# RackEth_rev_1.net
KiCad netlist of a schematic drawn in EasyEDA Pro
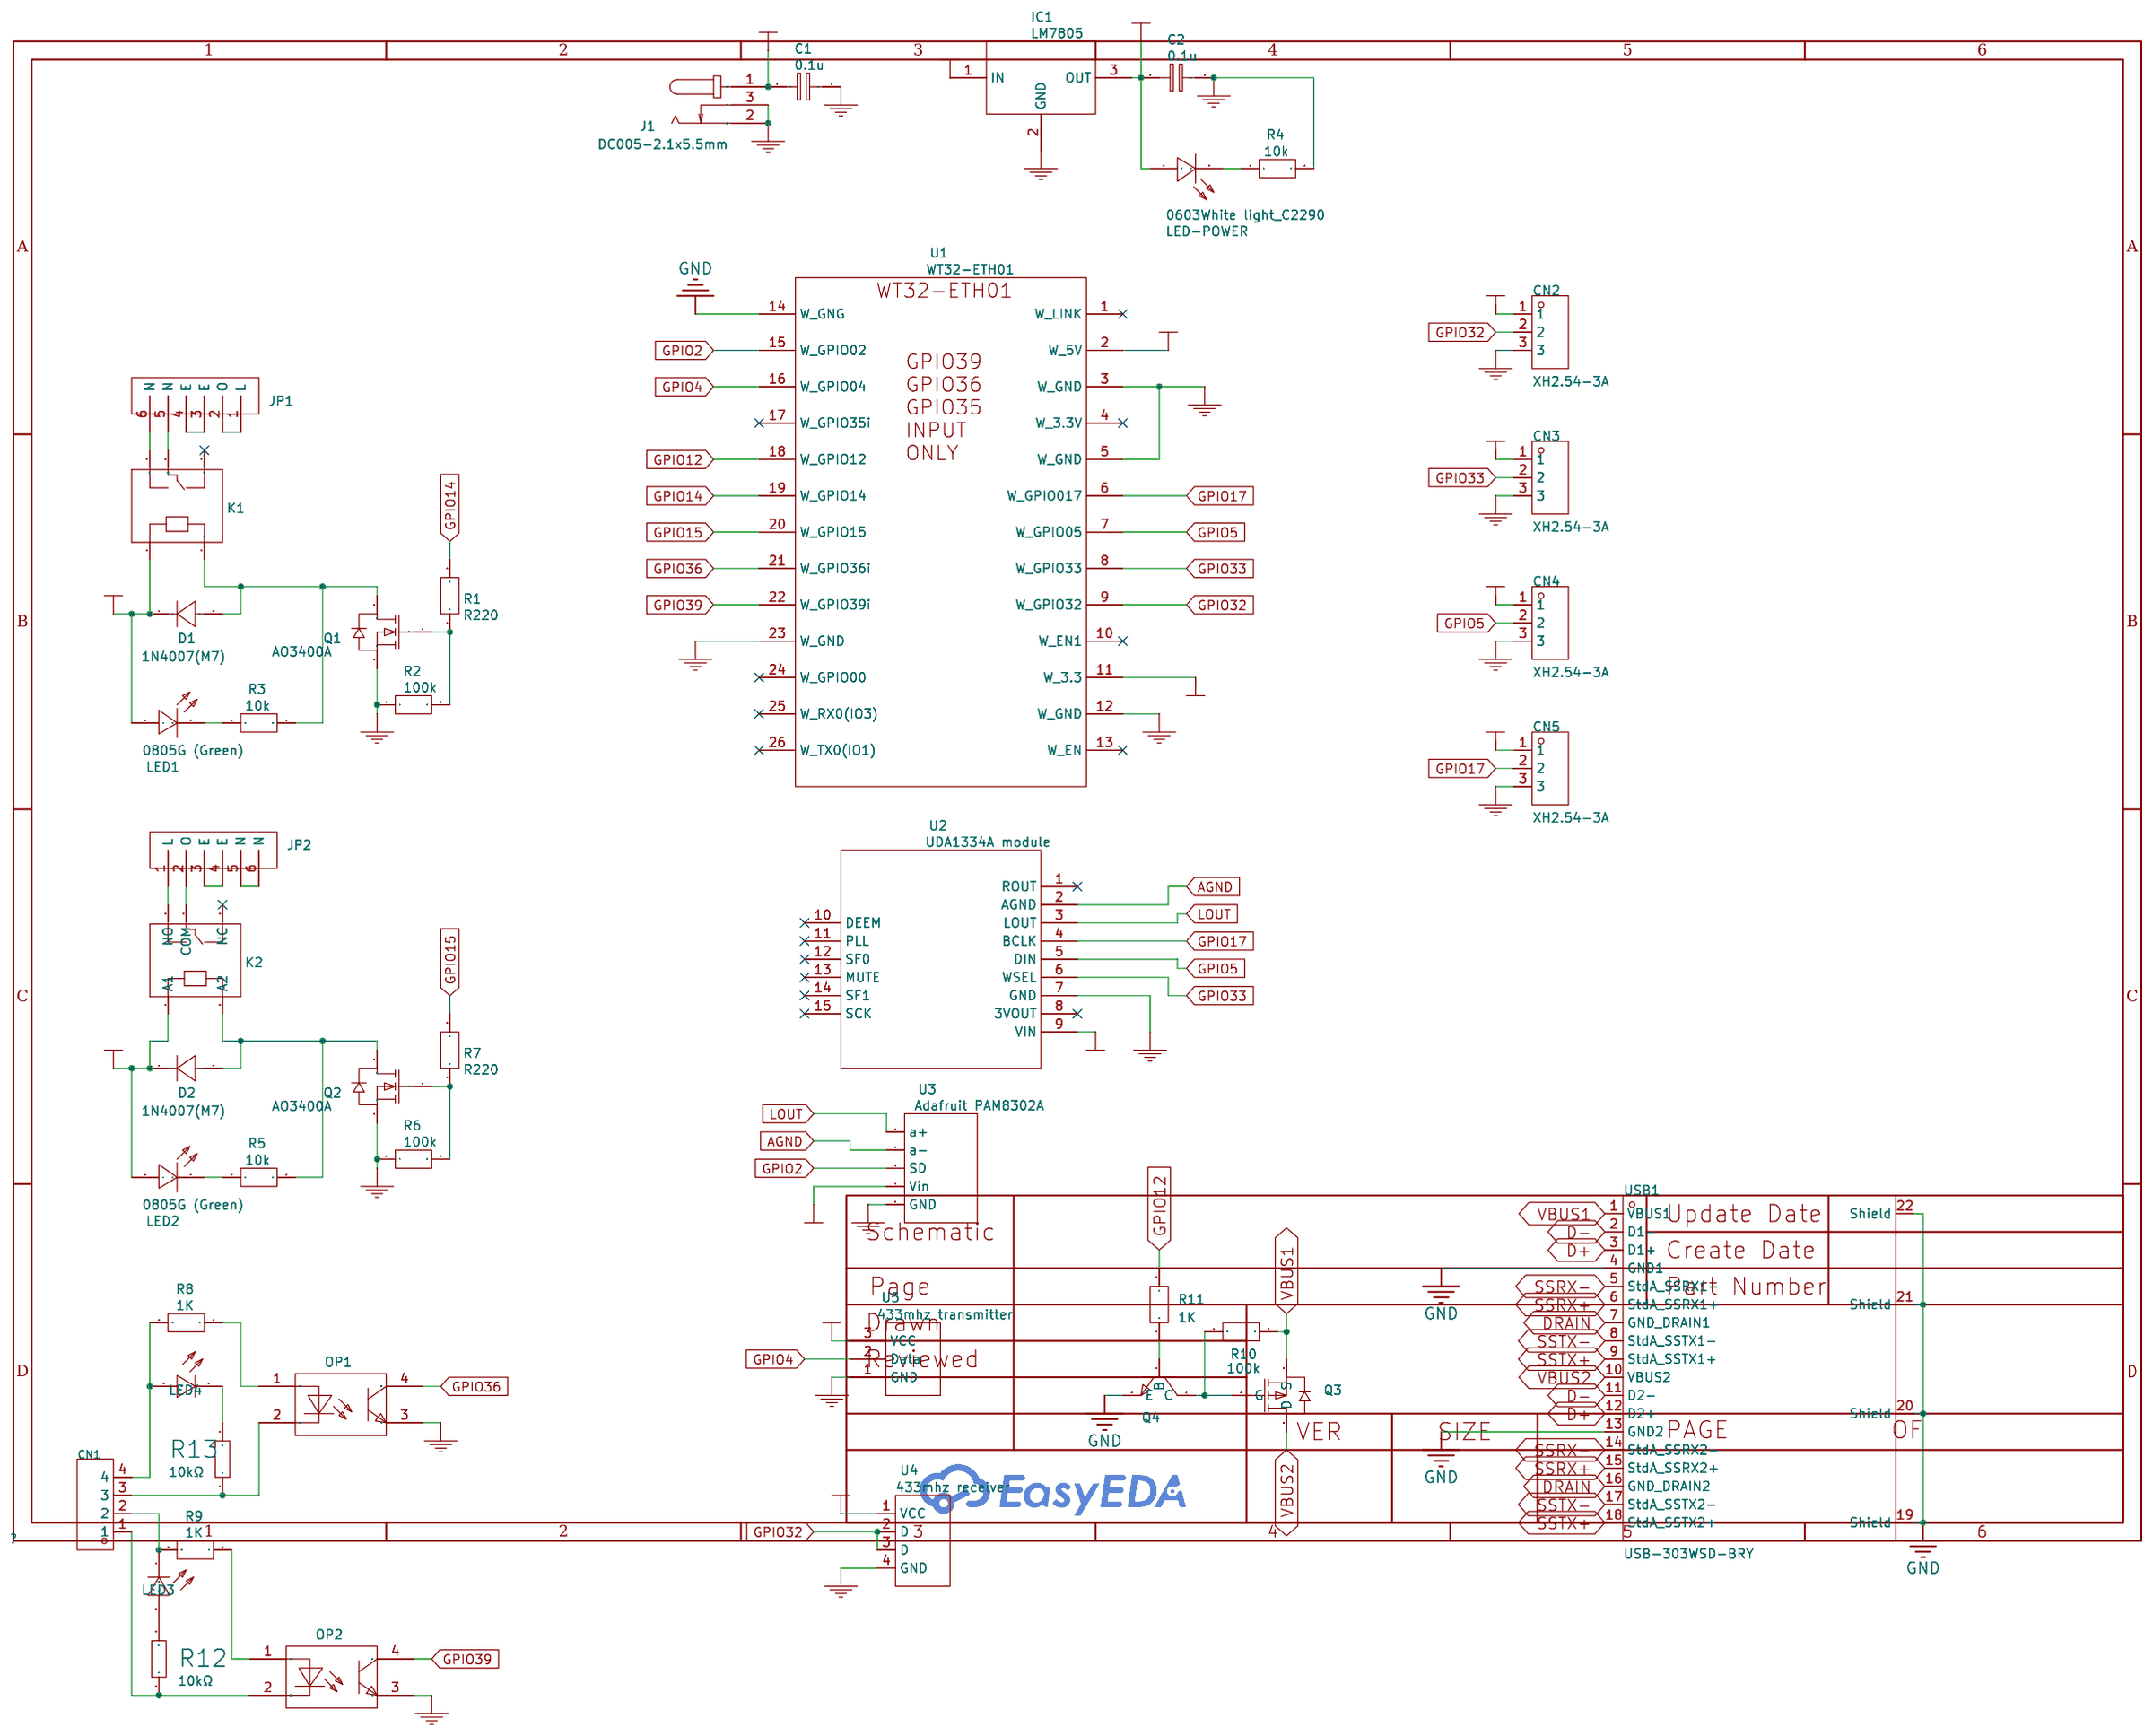
[diagram p0: schematic sheet]

(export (version "E")
  (design (tool "Eeschema 10.0.6"))
  (components
    (comp (ref "C1")
      (value "0.1u")
      (footprint "easyedapro:C0603")
      (fields
        (field (name "Manufacturer Part") "CL05B104KO5NNNC")
        (field (name "Manufacturer") "SAMSUNG(三星)")
      )
      (libsource (lib "easyedapro") (part "0.1u"))
    )
    (comp (ref "C2")
      (value "0.1u")
      (footprint "easyedapro:C0603")
      (fields
        (field (name "Manufacturer Part") "CL05B104KO5NNNC")
        (field (name "Manufacturer") "SAMSUNG(三星)")
      )
      (libsource (lib "easyedapro") (part "0.1u"))
    )
    (comp (ref "CN1")
      (value "WJ127-5.0-4P")
      (footprint "easyedapro:CONN-TH_4P-P5.00_WJ127-5.0-4P")
      (fields (field (name "Manufacturer") "KANGNEX(康奈克斯电气)"))
      (libsource (lib "easyedapro") (part "WJ127-5.0-4P"))
    )
    (comp (ref "CN2")
      (value "XH2.54-3A")
      (footprint "easyedapro:CONN-TH_3P-P2.50_HCTL_XH-3A-L")
      (libsource (lib "easyedapro") (part "XH2.54-3A"))
    )
    (comp (ref "CN3")
      (value "XH2.54-3A")
      (footprint "easyedapro:CONN-TH_3P-P2.50_HCTL_XH-3A-L")
      (libsource (lib "easyedapro") (part "XH2.54-3A"))
    )
    (comp (ref "CN4")
      (value "XH2.54-3A")
      (footprint "easyedapro:CONN-TH_3P-P2.50_HCTL_XH-3A-L")
      (libsource (lib "easyedapro") (part "XH2.54-3A"))
    )
    (comp (ref "CN5")
      (value "XH2.54-3A")
      (footprint "easyedapro:CONN-TH_3P-P2.50_HCTL_XH-3A-L")
      (libsource (lib "easyedapro") (part "XH2.54-3A"))
    )
    (comp (ref "D1")
      (value "1N4007(M7)")
      (footprint "easyedapro:SMA_L4.3-W2.7-LS5.1-RD")
      (fields (field (name "Manufacturer") "UMW(友台半导体)"))
      (libsource (lib "easyedapro") (part "1N4007(M7)"))
    )
    (comp (ref "D2")
      (value "1N4007(M7)")
      (footprint "easyedapro:SMA_L4.3-W2.7-LS5.1-RD")
      (fields (field (name "Manufacturer") "UMW(友台半导体)"))
      (libsource (lib "easyedapro") (part "1N4007(M7)"))
    )
    (comp (ref "IC1")
      (value "LM7805")
      (footprint "easyedapro:LM7805")
      (libsource (lib "easyedapro") (part "LM7805"))
    )
    (comp (ref "J1")
      (value "DC005-2.1x5.5mm")
      (footprint "easyedapro:DC-IN-TH_POWER-JACK")
      (fields (field (name "Manufacturer Part") "POWER-JACK") (field (name "Manufacturer") "索峰"))
      (libsource (lib "easyedapro") (part "DC005-2.1x5.5mm"))
    )
    (comp (ref "JP1") (value "JP1") (libsource (lib "easyedapro") (part "Terminal?")))
    (comp (ref "JP2") (value "JP2") (libsource (lib "easyedapro") (part "Terminal?")))
    (comp (ref "K1")
      (value "Relay1")
      (footprint "easyedapro:SRD-05VDC-SL-C_RELAY_SRD-05VDC-SL-C")
      (libsource (lib "easyedapro") (part "Relay1"))
    )
    (comp (ref "K2")
      (value "Relay2")
      (footprint "easyedapro:SRD-05VDC-SL-C_RELAY_SRD-05VDC-SL-C")
      (libsource (lib "easyedapro") (part "Relay2"))
    )
    (comp (ref "LED-POWER")
      (value "0603White light_C2290")
      (footprint "easyedapro:LED0603-R-RD_WHITE")
      (fields (field (name "Manufacturer Part") "KT-0603W") (field (name "Manufacturer") "KENTO"))
      (libsource (lib "easyedapro") (part "0603White light_C2290"))
    )
    (comp (ref "LED1")
      (value "0805G (Green)")
      (footprint "easyedapro:LED0805-RD_GREEN")
      (fields (field (name "Manufacturer") "KENTO"))
      (libsource (lib "easyedapro") (part "0805G (Green)"))
    )
    (comp (ref "LED2")
      (value "0805G (Green)")
      (footprint "easyedapro:LED0805-RD_GREEN")
      (fields (field (name "Manufacturer") "KENTO"))
      (libsource (lib "easyedapro") (part "0805G (Green)"))
    )
    (comp (ref "LED3")
      (value "19-213/Y2C-CQ2R2L/3T(CY)")
      (footprint "easyedapro:LED0603-RD-YELLOW")
      (fields (field (name "Manufacturer") "EVERLIGHT(亿光)"))
      (libsource (lib "easyedapro") (part "19-213/Y2C-CQ2R2L/3T(CY)"))
    )
    (comp (ref "LED4")
      (value "19-213/Y2C-CQ2R2L/3T(CY)")
      (footprint "easyedapro:LED0603-RD-YELLOW")
      (fields (field (name "Manufacturer") "EVERLIGHT(亿光)"))
      (libsource (lib "easyedapro") (part "19-213/Y2C-CQ2R2L/3T(CY)"))
    )
    (comp (ref "OP1")
      (value "EL817S1(C)(TU)-F")
      (footprint "easyedapro:OPTO-SMD-4_L4.6-W6.5-P2.54-LS10.3-TL")
      (fields (field (name "Manufacturer") "EVERLIGHT(亿光)"))
      (libsource (lib "easyedapro") (part "EL817S1(C)(TU)-F"))
    )
    (comp (ref "OP2")
      (value "EL817S1(C)(TU)-F")
      (footprint "easyedapro:OPTO-SMD-4_L4.6-W6.5-P2.54-LS10.3-TL")
      (fields (field (name "Manufacturer") "EVERLIGHT(亿光)"))
      (libsource (lib "easyedapro") (part "EL817S1(C)(TU)-F"))
    )
    (comp (ref "Q1")
      (value "AO3400A")
      (footprint "easyedapro:SOT-23-3_L2.9-W1.6-P1.90-LS2.8-BR")
      (fields (field (name "Manufacturer") "AOS"))
      (libsource (lib "easyedapro") (part "AO3400A"))
    )
    (comp (ref "Q2")
      (value "AO3400A")
      (footprint "easyedapro:SOT-23-3_L2.9-W1.6-P1.90-LS2.8-BR")
      (fields (field (name "Manufacturer") "AOS"))
      (libsource (lib "easyedapro") (part "AO3400A"))
    )
    (comp (ref "Q3")
      (value "AO3401A")
      (footprint "easyedapro:SOT-23_L2.9-W1.3-P1.90-LS2.4-BR")
      (fields (field (name "Manufacturer") "AOS"))
      (libsource (lib "easyedapro") (part "AO3401A"))
    )
    (comp (ref "Q4")
      (value "MMBT3904(RANGE:100-300)")
      (footprint "easyedapro:SOT-23-3_L2.9-W1.3-P1.90-LS2.4-BR")
      (fields (field (name "Manufacturer") "CJ(江苏长电/长晶)"))
      (libsource (lib "easyedapro") (part "MMBT3904"))
    )
    (comp (ref "R1")
      (value "R220")
      (footprint "easyedapro:R0603")
      (fields
        (field (name "Manufacturer Part") "0603WAF2200T5E")
        (field (name "Manufacturer") "UNI-ROYAL(厚声)")
      )
      (libsource (lib "easyedapro") (part "R220"))
    )
    (comp (ref "R2")
      (value "100k")
      (footprint "easyedapro:R0603")
      (fields
        (field (name "Manufacturer Part") "0603WAF1003T5E")
        (field (name "Manufacturer") "UNI-ROYAL(厚声)")
      )
      (libsource (lib "easyedapro") (part "100k"))
    )
    (comp (ref "R3")
      (value "10k")
      (footprint "easyedapro:R0603")
      (fields
        (field (name "Manufacturer Part") "0603WAF1002T5E")
        (field (name "Manufacturer") "UNI-ROYAL(厚声)")
      )
      (libsource (lib "easyedapro") (part "10k"))
    )
    (comp (ref "R4")
      (value "10k")
      (footprint "easyedapro:R0603")
      (fields
        (field (name "Manufacturer Part") "0603WAF1002T5E")
        (field (name "Manufacturer") "UNI-ROYAL(厚声)")
      )
      (libsource (lib "easyedapro") (part "10k"))
    )
    (comp (ref "R5")
      (value "10k")
      (footprint "easyedapro:R0603")
      (fields
        (field (name "Manufacturer Part") "0603WAF1002T5E")
        (field (name "Manufacturer") "UNI-ROYAL(厚声)")
      )
      (libsource (lib "easyedapro") (part "10k"))
    )
    (comp (ref "R6")
      (value "100k")
      (footprint "easyedapro:R0603")
      (fields
        (field (name "Manufacturer Part") "0603WAF1003T5E")
        (field (name "Manufacturer") "UNI-ROYAL(厚声)")
      )
      (libsource (lib "easyedapro") (part "100k"))
    )
    (comp (ref "R7")
      (value "R220")
      (footprint "easyedapro:R0603")
      (fields
        (field (name "Manufacturer Part") "0603WAF2200T5E")
        (field (name "Manufacturer") "UNI-ROYAL(厚声)")
      )
      (libsource (lib "easyedapro") (part "R220"))
    )
    (comp (ref "R8")
      (value "1K")
      (footprint "easyedapro:R0603")
      (fields
        (field (name "Manufacturer Part") "0603WAF2200T5E")
        (field (name "Manufacturer") "UNI-ROYAL(厚声)")
      )
      (libsource (lib "easyedapro") (part "1K"))
    )
    (comp (ref "R9")
      (value "1K")
      (footprint "easyedapro:R0603")
      (fields
        (field (name "Manufacturer Part") "0603WAF2200T5E")
        (field (name "Manufacturer") "UNI-ROYAL(厚声)")
      )
      (libsource (lib "easyedapro") (part "1K"))
    )
    (comp (ref "R10")
      (value "100k")
      (footprint "easyedapro:R0603")
      (fields
        (field (name "Manufacturer Part") "0603WAF1003T5E")
        (field (name "Manufacturer") "UNI-ROYAL(厚声)")
      )
      (libsource (lib "easyedapro") (part "100k"))
    )
    (comp (ref "R11")
      (value "1K")
      (footprint "easyedapro:R0603")
      (fields
        (field (name "Manufacturer Part") "0603WAF2200T5E")
        (field (name "Manufacturer") "UNI-ROYAL(厚声)")
      )
      (libsource (lib "easyedapro") (part "1K"))
    )
    (comp (ref "R12")
      (value "10kΩ")
      (footprint "easyedapro:R0603")
      (fields
        (field (name "Manufacturer Part") "0603WAF1002T5E")
        (field (name "Manufacturer") "UNI-ROYAL(厚声)")
      )
      (libsource (lib "easyedapro") (part "0603WAF1002T5E"))
    )
    (comp (ref "R13")
      (value "10kΩ")
      (footprint "easyedapro:R0603")
      (fields
        (field (name "Manufacturer Part") "0603WAF1002T5E")
        (field (name "Manufacturer") "UNI-ROYAL(厚声)")
      )
      (libsource (lib "easyedapro") (part "0603WAF1002T5E"))
    )
    (comp (ref "U1")
      (value "WT32-ETH01")
      (footprint "easyedapro:WT32-ETH01-M")
      (fields (field (name "Manufacturer") "Wireless-Tag"))
      (libsource (lib "easyedapro") (part "WT32-ETH01"))
    )
    (comp (ref "U2")
      (value "UDA1334A module")
      (footprint "easyedapro:UDA1334A_MODULE")
      (libsource (lib "easyedapro") (part "UDA1334A module"))
    )
    (comp (ref "U3")
      (value "Adafruit PAM8302A")
      (footprint "easyedapro:ADAFRUIT PAM8302A")
      (libsource (lib "easyedapro") (part "Adafruit PAM8302A"))
    )
    (comp (ref "U4")
      (value "433mhz receiver")
      (footprint "easyedapro:433MHZ-RECEIVER-PINS")
      (libsource (lib "easyedapro") (part "433mhz receiver"))
    )
    (comp (ref "U5")
      (value "433mhz transmitter")
      (footprint "easyedapro:RF-TRANSMITTER (433MHZ)")
      (libsource (lib "easyedapro") (part "433mhz transmitter"))
    )
    (comp (ref "USB1")
      (value "USB-303WSD-BRY")
      (footprint "easyedapro:USB-A-TH_XUNPU_USB-303WSD-BRY")
      (fields (field (name "Manufacturer") "XUNPU(讯普)"))
      (libsource (lib "easyedapro") (part "USB-303WSD-BRY"))
    )
  )
  (nets
    (net (code "1") (name "+3.3V") (class "Default")
      (node (ref "CN2") (pin "1") (pinfunction "1_1") (pintype "unspecified"))
      (node (ref "CN3") (pin "1") (pinfunction "1_1") (pintype "unspecified"))
      (node (ref "CN4") (pin "1") (pinfunction "1_1") (pintype "unspecified"))
      (node (ref "CN5") (pin "1") (pinfunction "1_1") (pintype "unspecified"))
      (node (ref "U1") (pin "11") (pinfunction "W_3.3_11") (pintype "unspecified"))
    )
    (net (code "2") (name "+5V") (class "Default")
      (node (ref "C2") (pin "1") (pinfunction "1_1") (pintype "unspecified"))
      (node (ref "D1") (pin "1") (pinfunction "K_1") (pintype "unspecified"))
      (node (ref "D2") (pin "1") (pinfunction "K_1") (pintype "unspecified"))
      (node (ref "IC1") (pin "3") (pinfunction "OUT_3") (pintype "unspecified"))
      (node (ref "K1") (pin "A1") (pinfunction "A1_A1") (pintype "unspecified"))
      (node (ref "K2") (pin "A1") (pinfunction "A1_A1") (pintype "unspecified"))
      (node (ref "LED-POWER") (pin "1") (pinfunction "A_1") (pintype "unspecified"))
      (node (ref "LED1") (pin "2") (pinfunction "A_2") (pintype "unspecified"))
      (node (ref "LED2") (pin "2") (pinfunction "A_2") (pintype "unspecified"))
      (node (ref "U1") (pin "2") (pinfunction "W_5V_2") (pintype "unspecified"))
      (node (ref "U2") (pin "9") (pinfunction "VIN_9") (pintype "unspecified"))
      (node (ref "U3") (pin "4") (pinfunction "Vin_4") (pintype "input"))
      (node (ref "U4") (pin "1") (pinfunction "VCC_1") (pintype "unspecified"))
      (node (ref "U5") (pin "3") (pinfunction "VCC_3") (pintype "bidirectional"))
    )
    (net (code "3") (name "AGND") (class "Default")
      (node (ref "U2") (pin "2") (pinfunction "AGND_2") (pintype "unspecified"))
      (node (ref "U3") (pin "2") (pinfunction "a-_2") (pintype "input"))
    )
    (net (code "4") (name "D+") (class "Default")
      (node (ref "USB1") (pin "12") (pinfunction "D2+_12") (pintype "unspecified"))
      (node (ref "USB1") (pin "3") (pinfunction "D1+_3") (pintype "unspecified"))
    )
    (net (code "5") (name "D-") (class "Default")
      (node (ref "USB1") (pin "11") (pinfunction "D2-_11") (pintype "unspecified"))
      (node (ref "USB1") (pin "2") (pinfunction "D1-_2") (pintype "unspecified"))
    )
    (net (code "6") (name "DRAIN") (class "Default")
      (node (ref "USB1") (pin "16") (pinfunction "GND_DRAIN2_16") (pintype "unspecified"))
      (node (ref "USB1") (pin "7") (pinfunction "GND_DRAIN1_7") (pintype "unspecified"))
    )
    (net (code "7") (name "GND") (class "Default")
      (node (ref "C1") (pin "2") (pinfunction "2_2") (pintype "unspecified"))
      (node (ref "C2") (pin "2") (pinfunction "2_2") (pintype "unspecified"))
      (node (ref "CN2") (pin "3") (pinfunction "3_3") (pintype "unspecified"))
      (node (ref "CN3") (pin "3") (pinfunction "3_3") (pintype "unspecified"))
      (node (ref "CN4") (pin "3") (pinfunction "3_3") (pintype "unspecified"))
      (node (ref "CN5") (pin "3") (pinfunction "3_3") (pintype "unspecified"))
      (node (ref "IC1") (pin "2") (pinfunction "GND_2") (pintype "unspecified"))
      (node (ref "J1") (pin "2") (pinfunction "GND_2") (pintype "unspecified"))
      (node (ref "J1") (pin "3") (pinfunction "3_3") (pintype "unspecified"))
      (node (ref "OP1") (pin "3") (pinfunction "EM_3") (pintype "unspecified"))
      (node (ref "OP2") (pin "3") (pinfunction "EM_3") (pintype "unspecified"))
      (node (ref "Q1") (pin "2") (pinfunction "S_2") (pintype "unspecified"))
      (node (ref "Q2") (pin "2") (pinfunction "S_2") (pintype "unspecified"))
      (node (ref "Q4") (pin "2") (pinfunction "E_2") (pintype "unspecified"))
      (node (ref "R2") (pin "1") (pinfunction "1_1") (pintype "unspecified"))
      (node (ref "R4") (pin "2") (pinfunction "2_2") (pintype "unspecified"))
      (node (ref "R6") (pin "1") (pinfunction "1_1") (pintype "unspecified"))
      (node (ref "U1") (pin "12") (pinfunction "W_GND_12") (pintype "unspecified"))
      (node (ref "U1") (pin "14") (pinfunction "W_GNG_14") (pintype "unspecified"))
      (node (ref "U1") (pin "23") (pinfunction "W_GND_23") (pintype "unspecified"))
      (node (ref "U1") (pin "3") (pinfunction "W_GND_3") (pintype "unspecified"))
      (node (ref "U1") (pin "5") (pinfunction "W_GND_5") (pintype "unspecified"))
      (node (ref "U2") (pin "7") (pinfunction "GND_7") (pintype "unspecified"))
      (node (ref "U3") (pin "5") (pinfunction "GND_5") (pintype "input"))
      (node (ref "U4") (pin "4") (pinfunction "GND_4") (pintype "unspecified"))
      (node (ref "U5") (pin "1") (pinfunction "GND_1") (pintype "bidirectional"))
      (node (ref "USB1") (pin "13") (pinfunction "GND2_13") (pintype "unspecified"))
      (node (ref "USB1") (pin "19") (pinfunction "Shield_19") (pintype "unspecified"))
      (node (ref "USB1") (pin "20") (pinfunction "Shield_20") (pintype "unspecified"))
      (node (ref "USB1") (pin "21") (pinfunction "Shield_21") (pintype "unspecified"))
      (node (ref "USB1") (pin "22") (pinfunction "Shield_22") (pintype "unspecified"))
      (node (ref "USB1") (pin "4") (pinfunction "GND1_4") (pintype "unspecified"))
    )
    (net (code "8") (name "GPIO2") (class "Default")
      (node (ref "U1") (pin "15") (pinfunction "W_GPIO02_15") (pintype "unspecified"))
      (node (ref "U3") (pin "3") (pinfunction "SD_3") (pintype "input"))
    )
    (net (code "9") (name "GPIO4") (class "Default")
      (node (ref "U1") (pin "16") (pinfunction "W_GPIO04_16") (pintype "unspecified"))
      (node (ref "U5") (pin "2") (pinfunction "Data_2") (pintype "bidirectional"))
    )
    (net (code "10") (name "GPIO5") (class "Default")
      (node (ref "CN4") (pin "2") (pinfunction "2_2") (pintype "unspecified"))
      (node (ref "U1") (pin "7") (pinfunction "W_GPIO05_7") (pintype "unspecified"))
      (node (ref "U2") (pin "5") (pinfunction "DIN_5") (pintype "unspecified"))
    )
    (net (code "11") (name "GPIO12") (class "Default")
      (node (ref "R11") (pin "2") (pinfunction "2_2") (pintype "unspecified"))
      (node (ref "U1") (pin "18") (pinfunction "W_GPIO12_18") (pintype "unspecified"))
    )
    (net (code "12") (name "GPIO14") (class "Default")
      (node (ref "R1") (pin "2") (pinfunction "2_2") (pintype "unspecified"))
      (node (ref "U1") (pin "19") (pinfunction "W_GPIO14_19") (pintype "unspecified"))
    )
    (net (code "13") (name "GPIO15") (class "Default")
      (node (ref "R7") (pin "2") (pinfunction "2_2") (pintype "unspecified"))
      (node (ref "U1") (pin "20") (pinfunction "W_GPIO15_20") (pintype "unspecified"))
    )
    (net (code "14") (name "GPIO17") (class "Default")
      (node (ref "CN5") (pin "2") (pinfunction "2_2") (pintype "unspecified"))
      (node (ref "U1") (pin "6") (pinfunction "W_GPIO017_6") (pintype "unspecified"))
      (node (ref "U2") (pin "4") (pinfunction "BCLK_4") (pintype "unspecified"))
    )
    (net (code "15") (name "GPIO32") (class "Default")
      (node (ref "CN2") (pin "2") (pinfunction "2_2") (pintype "unspecified"))
      (node (ref "U1") (pin "9") (pinfunction "W_GPIO32_9") (pintype "unspecified"))
      (node (ref "U4") (pin "2") (pinfunction "D_2") (pintype "unspecified"))
      (node (ref "U4") (pin "3") (pinfunction "D_3") (pintype "unspecified"))
    )
    (net (code "16") (name "GPIO33") (class "Default")
      (node (ref "CN3") (pin "2") (pinfunction "2_2") (pintype "unspecified"))
      (node (ref "U1") (pin "8") (pinfunction "W_GPIO33_8") (pintype "unspecified"))
      (node (ref "U2") (pin "6") (pinfunction "WSEL_6") (pintype "unspecified"))
    )
    (net (code "17") (name "GPIO36") (class "Default")
      (node (ref "OP1") (pin "4") (pinfunction "COL_4") (pintype "unspecified"))
      (node (ref "U1") (pin "21") (pinfunction "W_GPIO36i_21") (pintype "unspecified"))
    )
    (net (code "18") (name "GPIO39") (class "Default")
      (node (ref "OP2") (pin "4") (pinfunction "COL_4") (pintype "unspecified"))
      (node (ref "U1") (pin "22") (pinfunction "W_GPIO39i_22") (pintype "unspecified"))
    )
    (net (code "19") (name "LOUT") (class "Default")
      (node (ref "U2") (pin "3") (pinfunction "LOUT_3") (pintype "unspecified"))
      (node (ref "U3") (pin "1") (pinfunction "a+_1") (pintype "input"))
    )
    (net (code "20") (name "Net-(D1-A)") (class "Default")
      (node (ref "D1") (pin "2") (pinfunction "A_2") (pintype "unspecified"))
      (node (ref "K1") (pin "A2") (pinfunction "A2_A2") (pintype "unspecified"))
      (node (ref "Q1") (pin "3") (pinfunction "D_3") (pintype "unspecified"))
      (node (ref "R3") (pin "2") (pinfunction "2_2") (pintype "unspecified"))
    )
    (net (code "21") (name "Net-(D2-A)") (class "Default")
      (node (ref "D2") (pin "2") (pinfunction "A_2") (pintype "unspecified"))
      (node (ref "K2") (pin "A2") (pinfunction "A2_A2") (pintype "unspecified"))
      (node (ref "Q2") (pin "3") (pinfunction "D_3") (pintype "unspecified"))
      (node (ref "R5") (pin "2") (pinfunction "2_2") (pintype "unspecified"))
    )
    (net (code "22") (name "Net-(JP1-E-Pad3)") (class "Default")
      (node (ref "JP1") (pin "3") (pinfunction "E_3") (pintype "unspecified"))
      (node (ref "JP1") (pin "4") (pinfunction "E_4") (pintype "unspecified"))
    )
    (net (code "23") (name "Net-(JP1-L)") (class "Default")
      (node (ref "JP1") (pin "1") (pinfunction "L_1") (pintype "unspecified"))
      (node (ref "JP1") (pin "2") (pinfunction "O_2") (pintype "unspecified"))
    )
    (net (code "24") (name "Net-(JP1-N-Pad5)") (class "Default")
      (node (ref "JP1") (pin "5") (pinfunction "N_5") (pintype "unspecified"))
      (node (ref "K1") (pin "COM") (pinfunction "COM_COM") (pintype "unspecified"))
    )
    (net (code "25") (name "Net-(JP1-N-Pad6)") (class "Default")
      (node (ref "JP1") (pin "6") (pinfunction "N_6") (pintype "unspecified"))
      (node (ref "K1") (pin "NO") (pinfunction "NO_NO") (pintype "unspecified"))
    )
    (net (code "26") (name "Net-(JP2-E-Pad3)") (class "Default")
      (node (ref "JP2") (pin "3") (pinfunction "E_3") (pintype "unspecified"))
      (node (ref "JP2") (pin "4") (pinfunction "E_4") (pintype "unspecified"))
    )
    (net (code "27") (name "Net-(JP2-L)") (class "Default")
      (node (ref "JP2") (pin "1") (pinfunction "L_1") (pintype "unspecified"))
      (node (ref "K2") (pin "NO") (pinfunction "NO_NO") (pintype "unspecified"))
    )
    (net (code "28") (name "Net-(JP2-N-Pad5)") (class "Default")
      (node (ref "JP2") (pin "5") (pinfunction "N_5") (pintype "unspecified"))
      (node (ref "JP2") (pin "6") (pinfunction "N_6") (pintype "unspecified"))
    )
    (net (code "29") (name "Net-(JP2-O)") (class "Default")
      (node (ref "JP2") (pin "2") (pinfunction "O_2") (pintype "unspecified"))
      (node (ref "K2") (pin "COM") (pinfunction "COM_COM") (pintype "unspecified"))
    )
    (net (code "30") (name "Net-(LED-POWER-K)") (class "Default")
      (node (ref "LED-POWER") (pin "2") (pinfunction "K_2") (pintype "unspecified"))
      (node (ref "R4") (pin "1") (pinfunction "1_1") (pintype "unspecified"))
    )
    (net (code "31") (name "Net-(LED1-K)") (class "Default")
      (node (ref "LED1") (pin "1") (pinfunction "K_1") (pintype "unspecified"))
      (node (ref "R3") (pin "1") (pinfunction "1_1") (pintype "unspecified"))
    )
    (net (code "32") (name "Net-(LED2-K)") (class "Default")
      (node (ref "LED2") (pin "1") (pinfunction "K_1") (pintype "unspecified"))
      (node (ref "R5") (pin "1") (pinfunction "1_1") (pintype "unspecified"))
    )
    (net (code "33") (name "Net-(LED3-A)") (class "Default")
      (node (ref "LED3") (pin "2") (pinfunction "A_2") (pintype "input"))
      (node (ref "R12") (pin "2") (pinfunction "2_2") (pintype "input"))
    )
    (net (code "34") (name "Net-(LED3-C)") (class "Default")
      (node (ref "CN1") (pin "2") (pinfunction "2_2") (pintype "input"))
      (node (ref "LED3") (pin "1") (pinfunction "C_1") (pintype "input"))
      (node (ref "R9") (pin "2") (pinfunction "2_2") (pintype "unspecified"))
    )
    (net (code "35") (name "Net-(LED4-A)") (class "Default")
      (node (ref "CN1") (pin "4") (pinfunction "4_4") (pintype "input"))
      (node (ref "LED4") (pin "2") (pinfunction "A_2") (pintype "input"))
      (node (ref "R8") (pin "2") (pinfunction "2_2") (pintype "unspecified"))
    )
    (net (code "36") (name "Net-(LED4-C)") (class "Default")
      (node (ref "LED4") (pin "1") (pinfunction "C_1") (pintype "input"))
      (node (ref "R13") (pin "2") (pinfunction "2_2") (pintype "input"))
    )
    (net (code "37") (name "Net-(OP1-AN)") (class "Default")
      (node (ref "OP1") (pin "1") (pinfunction "AN_1") (pintype "unspecified"))
      (node (ref "R8") (pin "1") (pinfunction "1_1") (pintype "unspecified"))
    )
    (net (code "38") (name "Net-(OP1-CAT)") (class "Default")
      (node (ref "CN1") (pin "3") (pinfunction "3_3") (pintype "input"))
      (node (ref "OP1") (pin "2") (pinfunction "CAT_2") (pintype "unspecified"))
      (node (ref "R13") (pin "1") (pinfunction "1_1") (pintype "input"))
    )
    (net (code "39") (name "Net-(OP2-AN)") (class "Default")
      (node (ref "OP2") (pin "1") (pinfunction "AN_1") (pintype "unspecified"))
      (node (ref "R9") (pin "1") (pinfunction "1_1") (pintype "unspecified"))
    )
    (net (code "40") (name "Net-(OP2-CAT)") (class "Default")
      (node (ref "CN1") (pin "1") (pinfunction "1_1") (pintype "input"))
      (node (ref "OP2") (pin "2") (pinfunction "CAT_2") (pintype "unspecified"))
      (node (ref "R12") (pin "1") (pinfunction "1_1") (pintype "input"))
    )
    (net (code "41") (name "Net-(Q1-G)") (class "Default")
      (node (ref "Q1") (pin "1") (pinfunction "G_1") (pintype "unspecified"))
      (node (ref "R1") (pin "1") (pinfunction "1_1") (pintype "unspecified"))
      (node (ref "R2") (pin "2") (pinfunction "2_2") (pintype "unspecified"))
    )
    (net (code "42") (name "Net-(Q2-G)") (class "Default")
      (node (ref "Q2") (pin "1") (pinfunction "G_1") (pintype "unspecified"))
      (node (ref "R6") (pin "2") (pinfunction "2_2") (pintype "unspecified"))
      (node (ref "R7") (pin "1") (pinfunction "1_1") (pintype "unspecified"))
    )
    (net (code "43") (name "Net-(Q3-G)") (class "Default")
      (node (ref "Q3") (pin "1") (pinfunction "G_1") (pintype "unspecified"))
      (node (ref "Q4") (pin "3") (pinfunction "C_3") (pintype "unspecified"))
      (node (ref "R10") (pin "1") (pinfunction "1_1") (pintype "unspecified"))
    )
    (net (code "44") (name "Net-(Q4-B)") (class "Default")
      (node (ref "Q4") (pin "1") (pinfunction "B_1") (pintype "unspecified"))
      (node (ref "R11") (pin "1") (pinfunction "1_1") (pintype "unspecified"))
    )
    (net (code "45") (name "SSRX+") (class "Default")
      (node (ref "USB1") (pin "15") (pinfunction "StdA_SSRX2+_15") (pintype "unspecified"))
      (node (ref "USB1") (pin "6") (pinfunction "StdA_SSRX1+_6") (pintype "unspecified"))
    )
    (net (code "46") (name "SSRX-") (class "Default")
      (node (ref "USB1") (pin "14") (pinfunction "StdA_SSRX2-_14") (pintype "unspecified"))
      (node (ref "USB1") (pin "5") (pinfunction "StdA_SSRX1-_5") (pintype "unspecified"))
    )
    (net (code "47") (name "SSTX+") (class "Default")
      (node (ref "USB1") (pin "18") (pinfunction "StdA_SSTX2+_18") (pintype "unspecified"))
      (node (ref "USB1") (pin "9") (pinfunction "StdA_SSTX1+_9") (pintype "unspecified"))
    )
    (net (code "48") (name "SSTX-") (class "Default")
      (node (ref "USB1") (pin "17") (pinfunction "StdA_SSTX2-_17") (pintype "unspecified"))
      (node (ref "USB1") (pin "8") (pinfunction "StdA_SSTX1-_8") (pintype "unspecified"))
    )
    (net (code "49") (name "VBUS1") (class "Default")
      (node (ref "Q3") (pin "2") (pinfunction "S_2") (pintype "unspecified"))
      (node (ref "R10") (pin "2") (pinfunction "2_2") (pintype "unspecified"))
      (node (ref "USB1") (pin "1") (pinfunction "VBUS1_1") (pintype "unspecified"))
    )
    (net (code "50") (name "VBUS2") (class "Default")
      (node (ref "Q3") (pin "3") (pinfunction "D_3") (pintype "unspecified"))
      (node (ref "USB1") (pin "10") (pinfunction "VBUS2_10") (pintype "unspecified"))
    )
    (net (code "51") (name "VCC") (class "Default")
      (node (ref "C1") (pin "1") (pinfunction "1_1") (pintype "unspecified"))
      (node (ref "IC1") (pin "1") (pinfunction "IN_1") (pintype "unspecified"))
      (node (ref "J1") (pin "1") (pinfunction "VCC_1") (pintype "unspecified"))
    )
    (net (code "52") (name "unconnected-(K1-PadNC)") (class "Default")
      (node (ref "K1") (pin "NC") (pinfunction "NC_NC") (pintype "unspecified+no_connect"))
    )
    (net (code "53") (name "unconnected-(K2-PadNC)") (class "Default")
      (node (ref "K2") (pin "NC") (pinfunction "NC_NC") (pintype "unspecified+no_connect"))
    )
    (net (code "54") (name "unconnected-(U1-W_3.3V-Pad4)") (class "Default")
      (node (ref "U1") (pin "4") (pinfunction "W_3.3V_4") (pintype "unspecified+no_connect"))
    )
    (net (code "55") (name "unconnected-(U1-W_EN-Pad13)") (class "Default")
      (node (ref "U1") (pin "13") (pinfunction "W_EN_13") (pintype "unspecified+no_connect"))
    )
    (net (code "56") (name "unconnected-(U1-W_EN1-Pad10)") (class "Default")
      (node (ref "U1") (pin "10") (pinfunction "W_EN1_10") (pintype "unspecified+no_connect"))
    )
    (net (code "57") (name "unconnected-(U1-W_GPIO00-Pad24)") (class "Default")
      (node (ref "U1") (pin "24") (pinfunction "W_GPIO00_24") (pintype "unspecified+no_connect"))
    )
    (net (code "58") (name "unconnected-(U1-W_GPIO35i-Pad17)") (class "Default")
      (node (ref "U1") (pin "17") (pinfunction "W_GPIO35i_17") (pintype "unspecified+no_connect"))
    )
    (net (code "59") (name "unconnected-(U1-W_LINK-Pad1)") (class "Default")
      (node (ref "U1") (pin "1") (pinfunction "W_LINK_1") (pintype "unspecified+no_connect"))
    )
    (net (code "60") (name "unconnected-(U1-W_RX0(IO3)-Pad25)") (class "Default")
      (node (ref "U1") (pin "25") (pinfunction "W_RX0(IO3)_25") (pintype "unspecified+no_connect"))
    )
    (net (code "61") (name "unconnected-(U1-W_TX0(IO1)-Pad26)") (class "Default")
      (node (ref "U1") (pin "26") (pinfunction "W_TX0(IO1)_26") (pintype "unspecified+no_connect"))
    )
    (net (code "62") (name "unconnected-(U2-3VOUT-Pad8)") (class "Default")
      (node (ref "U2") (pin "8") (pinfunction "3VOUT_8") (pintype "unspecified+no_connect"))
    )
    (net (code "63") (name "unconnected-(U2-DEEM-Pad10)") (class "Default")
      (node (ref "U2") (pin "10") (pinfunction "DEEM_10") (pintype "unspecified+no_connect"))
    )
    (net (code "64") (name "unconnected-(U2-MUTE-Pad13)") (class "Default")
      (node (ref "U2") (pin "13") (pinfunction "MUTE_13") (pintype "unspecified+no_connect"))
    )
    (net (code "65") (name "unconnected-(U2-PLL-Pad11)") (class "Default")
      (node (ref "U2") (pin "11") (pinfunction "PLL_11") (pintype "unspecified+no_connect"))
    )
    (net (code "66") (name "unconnected-(U2-ROUT-Pad1)") (class "Default")
      (node (ref "U2") (pin "1") (pinfunction "ROUT_1") (pintype "unspecified+no_connect"))
    )
    (net (code "67") (name "unconnected-(U2-SCK-Pad15)") (class "Default")
      (node (ref "U2") (pin "15") (pinfunction "SCK_15") (pintype "unspecified+no_connect"))
    )
    (net (code "68") (name "unconnected-(U2-SF0-Pad12)") (class "Default")
      (node (ref "U2") (pin "12") (pinfunction "SF0_12") (pintype "unspecified+no_connect"))
    )
    (net (code "69") (name "unconnected-(U2-SF1-Pad14)") (class "Default")
      (node (ref "U2") (pin "14") (pinfunction "SF1_14") (pintype "unspecified+no_connect"))
    )
  )
)
